# Barun_Module.net
KiCad netlist of a schematic drawn in Altium Designer
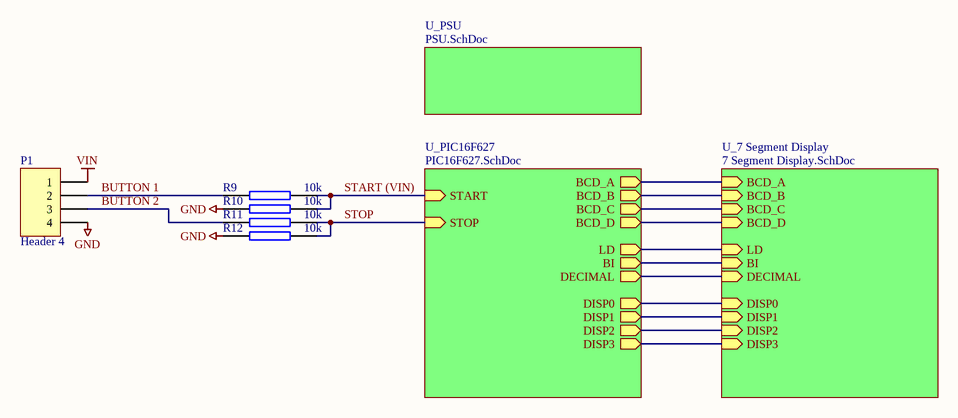
[diagram p0: Barun Module.SchDoc]

(export (version "E")
  (design (tool "Eeschema 10.0.6"))
  (components
    (comp (ref "P1")
      (value "Header 4")
      (footprint "4 x 5.08mm")
      (description "Header, 4-Pin")
      (fields
        (field (name "MANUFACTURER") "Phoenix Contact")
        (field (name "MANUFACTURER PART NO.") "1733596")
      )
      (libsource (lib "Miscellaneous Connectors") (part "Header 4"))
    )
    (comp (ref "R9")
      (value "10k")
      (footprint "RES (3D) - 0603")
      (description "RESISTOR SMD 0603 10k")
      (fields (field (name "MOUSER PART NO.") "652-CR0603FX-1002ELF") (field (name "MANUFACTURER") "Bourns"))
      (libsource (lib "NASCO Resistors") (part "RES SMD 0603 10k"))
    )
    (comp (ref "R10")
      (value "10k")
      (footprint "RES (3D) - 0603")
      (description "RESISTOR SMD 0603 10k")
      (fields (field (name "MOUSER PART NO.") "652-CR0603FX-1002ELF") (field (name "MANUFACTURER") "Bourns"))
      (libsource (lib "NASCO Resistors") (part "RES SMD 0603 10k"))
    )
    (comp (ref "R11")
      (value "10k")
      (footprint "RES (3D) - 0603")
      (description "RESISTOR SMD 0603 10k")
      (fields (field (name "MOUSER PART NO.") "652-CR0603FX-1002ELF") (field (name "MANUFACTURER") "Bourns"))
      (libsource (lib "NASCO Resistors") (part "RES SMD 0603 10k"))
    )
    (comp (ref "R12")
      (value "10k")
      (footprint "RES (3D) - 0603")
      (description "RESISTOR SMD 0603 10k")
      (fields (field (name "MOUSER PART NO.") "652-CR0603FX-1002ELF") (field (name "MANUFACTURER") "Bourns"))
      (libsource (lib "NASCO Resistors") (part "RES SMD 0603 10k"))
    )
  )
  (nets
    (net (code "6") (name "/BUTTON 1") (class "Default")
      (node (ref "P1") (pin "2") (pinfunction "2_2") (pintype "passive"))
      (node (ref "R9") (pin "1") (pinfunction "1_1") (pintype "passive"))
    )
    (net (code "7") (name "/BUTTON 2") (class "Default")
      (node (ref "P1") (pin "3") (pinfunction "3_3") (pintype "passive"))
      (node (ref "R11") (pin "1") (pinfunction "1_1") (pintype "passive"))
    )
    (net (code "14") (name "/START (VIN)") (class "Default")
      (node (ref "R10") (pin "2") (pinfunction "2_2") (pintype "passive"))
      (node (ref "R9") (pin "2") (pinfunction "2_2") (pintype "passive"))
    )
    (net (code "15") (name "/STOP") (class "Default")
      (node (ref "R11") (pin "2") (pinfunction "2_2") (pintype "passive"))
      (node (ref "R12") (pin "2") (pinfunction "2_2") (pintype "passive"))
    )
    (net (code "16") (name "GND") (class "Default")
      (node (ref "P1") (pin "4") (pinfunction "4_4") (pintype "passive"))
      (node (ref "R10") (pin "1") (pinfunction "1_1") (pintype "passive"))
      (node (ref "R12") (pin "1") (pinfunction "1_1") (pintype "passive"))
    )
    (net (code "17") (name "VIN") (class "Default")
      (node (ref "P1") (pin "1") (pinfunction "1_1") (pintype "passive"))
    )
  )
)
